# main.net
KiCad netlist of a schematic drawn in EAGLE
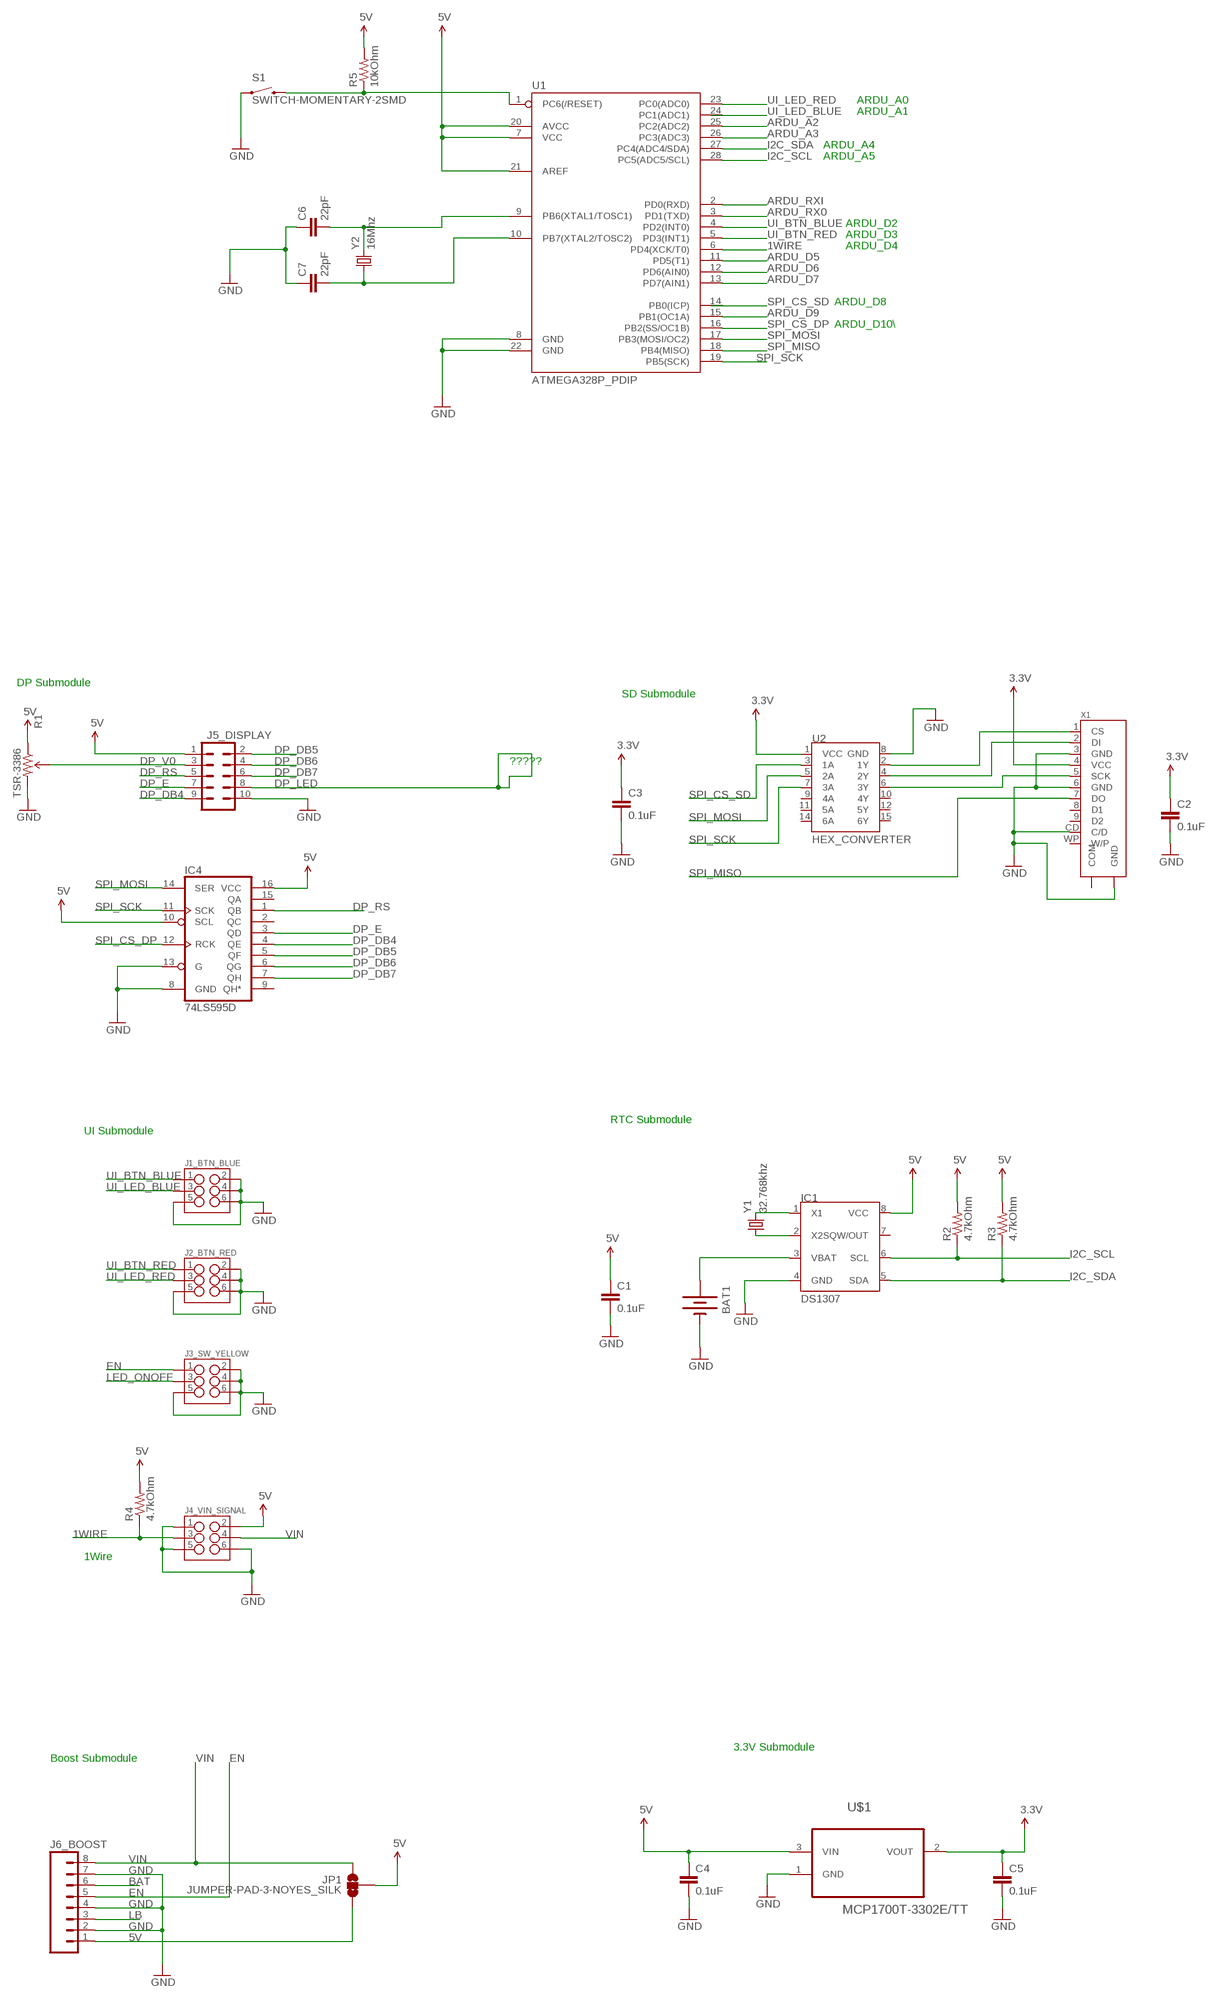
[diagram p0: schematic, sheet 1]

(export (version "E")
  (design (tool "Eeschema 10.0.6"))
  (components
    (comp (ref "BAT1")
      (value "BATTERY20PTH")
      (footprint "eagle-import:BATTCOM_20MM_PTH")
      (libsource (lib "eagle-import") (part "BATTERY20PTH"))
    )
    (comp (ref "C1")
      (value "0.1uF")
      (footprint "eagle-import:1206")
      (libsource (lib "eagle-import") (part "CAP1206"))
    )
    (comp (ref "C2")
      (value "0.1uF")
      (footprint "eagle-import:1206")
      (libsource (lib "eagle-import") (part "CAP1206"))
    )
    (comp (ref "C3")
      (value "0.1uF")
      (footprint "eagle-import:1206")
      (libsource (lib "eagle-import") (part "CAP1206"))
    )
    (comp (ref "C4")
      (value "0.1uF")
      (footprint "eagle-import:1206")
      (libsource (lib "eagle-import") (part "CAP1206"))
    )
    (comp (ref "C5")
      (value "0.1uF")
      (footprint "eagle-import:1206")
      (libsource (lib "eagle-import") (part "CAP1206"))
    )
    (comp (ref "C6")
      (value "22pF")
      (footprint "eagle-import:1206")
      (libsource (lib "eagle-import") (part "CAP1206"))
    )
    (comp (ref "C7")
      (value "22pF")
      (footprint "eagle-import:1206")
      (libsource (lib "eagle-import") (part "CAP1206"))
    )
    (comp (ref "IC1")
      (value "DS1307")
      (footprint "eagle-import:SOIC-8")
      (libsource (lib "eagle-import") (part "DS1307"))
    )
    (comp (ref "IC4")
      (value "74LS595D")
      (footprint "eagle-import:SO16")
      (libsource (lib "eagle-import") (part "74595DLS"))
    )
    (comp (ref "J1_BTN_BLUE")
      (value "M03X2SHROUD")
      (footprint "eagle-import:2X3-SHROUDED")
      (libsource (lib "eagle-import") (part "M03X2SHROUD"))
    )
    (comp (ref "J2_BTN_RED")
      (value "M03X2SHROUD")
      (footprint "eagle-import:2X3-SHROUDED")
      (libsource (lib "eagle-import") (part "M03X2SHROUD"))
    )
    (comp (ref "J3_SW_YELLOW")
      (value "M03X2SHROUD")
      (footprint "eagle-import:2X3-SHROUDED")
      (libsource (lib "eagle-import") (part "M03X2SHROUD"))
    )
    (comp (ref "J4_VIN_SIGNAL")
      (value "M03X2SHROUD")
      (footprint "eagle-import:2X3-SHROUDED")
      (libsource (lib "eagle-import") (part "M03X2SHROUD"))
    )
    (comp (ref "J5_DISPLAY")
      (value "M05X2SHD")
      (footprint "eagle-import:2X5-SHROUDED")
      (libsource (lib "eagle-import") (part "M05X2SHD"))
    )
    (comp (ref "J6_BOOST")
      (value "M08")
      (footprint "eagle-import:1X08_ROUND")
      (libsource (lib "eagle-import") (part "M08"))
    )
    (comp (ref "JP1")
      (value "JUMPER-PAD-3-NOYES_SILK")
      (footprint "eagle-import:PAD-JUMPER-3-NO_YES_SILK")
      (libsource (lib "eagle-import") (part "JUMPER-PAD-3-NOYES_SILK"))
    )
    (comp (ref "R1")
      (value "TSR-3386")
      (footprint "eagle-import:3386U")
      (libsource (lib "eagle-import") (part "TRIMPOT-PTH-KNOB"))
    )
    (comp (ref "R2")
      (value "4.7kOhm")
      (footprint "eagle-import:1206")
      (libsource (lib "eagle-import") (part "RESISTOR1206"))
    )
    (comp (ref "R3")
      (value "4.7kOhm")
      (footprint "eagle-import:1206")
      (libsource (lib "eagle-import") (part "RESISTOR1206"))
    )
    (comp (ref "R4")
      (value "4.7kOhm")
      (footprint "eagle-import:1206")
      (libsource (lib "eagle-import") (part "RESISTOR1206"))
    )
    (comp (ref "R5")
      (value "10kOhm")
      (footprint "eagle-import:1206")
      (libsource (lib "eagle-import") (part "RESISTOR1206"))
    )
    (comp (ref "S1")
      (value "SWITCH-MOMENTARY-2SMD")
      (footprint "eagle-import:TACTILE-SWITCH-SMD")
      (libsource (lib "eagle-import") (part "SWITCH-MOMENTARY-2SMD"))
    )
    (comp (ref "U$1")
      (value "MCP1700T-3302E/TT")
      (footprint "eagle-import:SOT95P237X112-3N")
      (libsource (lib "eagle-import") (part "MCP1700T-3302E/TT"))
    )
    (comp (ref "U1")
      (value "ATMEGA328P_PDIP")
      (footprint "eagle-import:DIL28-3")
      (libsource (lib "eagle-import") (part "ATMEGA328P_PDIP"))
    )
    (comp (ref "U2")
      (value "HEX_CONVERTER")
      (footprint "eagle-import:SO016")
      (libsource (lib "eagle-import") (part "HEX_CONVERTER"))
    )
    (comp (ref "X1")
      (value "SD-SOCKET-AVX")
      (footprint "eagle-import:SD-SOCKET-AVX")
      (libsource (lib "eagle-import") (part "SD-SOCKET-AVX"))
    )
    (comp (ref "Y1")
      (value "32.768khz")
      (footprint "eagle-import:CRYSTAL-32KHZ-SMD-MELF")
      (libsource (lib "eagle-import") (part "CRYSTAL32-SMD-MELF"))
    )
    (comp (ref "Y2")
      (value "16Mhz")
      (footprint "eagle-import:HC49US")
      (libsource (lib "eagle-import") (part "CRYSTALHC49US"))
    )
  )
  (nets
    (net (code "1") (name "/1WIRE") (class "Default")
      (node (ref "J4_VIN_SIGNAL") (pin "3") (pinfunction "3_3") (pintype "bidirectional"))
      (node (ref "R4") (pin "1") (pinfunction "1_1") (pintype "passive"))
      (node (ref "U1") (pin "6") (pinfunction "PD4(XCK/T0)_6") (pintype "bidirectional"))
    )
    (net (code "2") (name "/ARDU_A2") (class "Default")
      (node (ref "U1") (pin "25") (pinfunction "PC2(ADC2)_25") (pintype "bidirectional"))
    )
    (net (code "3") (name "/ARDU_A3") (class "Default")
      (node (ref "U1") (pin "26") (pinfunction "PC3(ADC3)_26") (pintype "bidirectional"))
    )
    (net (code "4") (name "/ARDU_D5") (class "Default")
      (node (ref "U1") (pin "11") (pinfunction "PD5(T1)_11") (pintype "bidirectional"))
    )
    (net (code "5") (name "/ARDU_D6") (class "Default")
      (node (ref "U1") (pin "12") (pinfunction "PD6(AIN0)_12") (pintype "bidirectional"))
    )
    (net (code "6") (name "/ARDU_D7") (class "Default")
      (node (ref "U1") (pin "13") (pinfunction "PD7(AIN1)_13") (pintype "bidirectional"))
    )
    (net (code "7") (name "/ARDU_D9") (class "Default")
      (node (ref "U1") (pin "15") (pinfunction "PB1(OC1A)_15") (pintype "bidirectional"))
    )
    (net (code "8") (name "/ARDU_RX0") (class "Default")
      (node (ref "U1") (pin "3") (pinfunction "PD1(TXD)_3") (pintype "bidirectional"))
    )
    (net (code "9") (name "/ARDU_RXI") (class "Default")
      (node (ref "U1") (pin "2") (pinfunction "PD0(RXD)_2") (pintype "bidirectional"))
    )
    (net (code "10") (name "/BAT") (class "Default")
      (node (ref "J6_BOOST") (pin "6") (pinfunction "6_6") (pintype "passive"))
    )
    (net (code "11") (name "/DP_DB4") (class "Default")
      (node (ref "IC4") (pin "4") (pinfunction "QE_4") (pintype "tri_state"))
      (node (ref "J5_DISPLAY") (pin "9") (pinfunction "9_9") (pintype "passive"))
    )
    (net (code "12") (name "/DP_DB5") (class "Default")
      (node (ref "IC4") (pin "5") (pinfunction "QF_5") (pintype "tri_state"))
      (node (ref "J5_DISPLAY") (pin "2") (pinfunction "2_2") (pintype "passive"))
    )
    (net (code "13") (name "/DP_DB6") (class "Default")
      (node (ref "IC4") (pin "6") (pinfunction "QG_6") (pintype "tri_state"))
      (node (ref "J5_DISPLAY") (pin "4") (pinfunction "4_4") (pintype "passive"))
    )
    (net (code "14") (name "/DP_DB7") (class "Default")
      (node (ref "IC4") (pin "7") (pinfunction "QH_7") (pintype "tri_state"))
      (node (ref "J5_DISPLAY") (pin "6") (pinfunction "6_6") (pintype "passive"))
    )
    (net (code "15") (name "/DP_E") (class "Default")
      (node (ref "IC4") (pin "3") (pinfunction "QD_3") (pintype "tri_state"))
      (node (ref "J5_DISPLAY") (pin "7") (pinfunction "7_7") (pintype "passive"))
    )
    (net (code "16") (name "/DP_LED") (class "Default")
      (node (ref "J5_DISPLAY") (pin "8") (pinfunction "8_8") (pintype "passive"))
    )
    (net (code "17") (name "/DP_RS") (class "Default")
      (node (ref "IC4") (pin "1") (pinfunction "QB_1") (pintype "tri_state"))
      (node (ref "J5_DISPLAY") (pin "5") (pinfunction "5_5") (pintype "passive"))
    )
    (net (code "18") (name "/DP_V0") (class "Default")
      (node (ref "J5_DISPLAY") (pin "3") (pinfunction "3_3") (pintype "passive"))
      (node (ref "R1") (pin "2") (pinfunction "WIPER_2") (pintype "passive"))
    )
    (net (code "19") (name "/EN") (class "Default")
      (node (ref "J3_SW_YELLOW") (pin "1") (pinfunction "1_1") (pintype "bidirectional"))
      (node (ref "J6_BOOST") (pin "5") (pinfunction "5_5") (pintype "passive"))
    )
    (net (code "20") (name "/I2C_SCL") (class "Default")
      (node (ref "IC1") (pin "6") (pinfunction "SCL_6") (pintype "input"))
      (node (ref "R2") (pin "1") (pinfunction "1_1") (pintype "passive"))
      (node (ref "U1") (pin "28") (pinfunction "PC5(ADC5/SCL)_28") (pintype "bidirectional"))
    )
    (net (code "21") (name "/I2C_SDA") (class "Default")
      (node (ref "IC1") (pin "5") (pinfunction "SDA_5") (pintype "bidirectional"))
      (node (ref "R3") (pin "1") (pinfunction "1_1") (pintype "passive"))
      (node (ref "U1") (pin "27") (pinfunction "PC4(ADC4/SDA)_27") (pintype "bidirectional"))
    )
    (net (code "22") (name "/LB") (class "Default")
      (node (ref "J6_BOOST") (pin "3") (pinfunction "3_3") (pintype "passive"))
    )
    (net (code "23") (name "/LED_ONOFF") (class "Default")
      (node (ref "J3_SW_YELLOW") (pin "3") (pinfunction "3_3") (pintype "bidirectional"))
    )
    (net (code "24") (name "/SPI_CS_DP") (class "Default")
      (node (ref "IC4") (pin "12") (pinfunction "RCK_12") (pintype "input"))
      (node (ref "U1") (pin "16") (pinfunction "PB2(SS/OC1B)_16") (pintype "bidirectional"))
    )
    (net (code "25") (name "/SPI_CS_SD") (class "Default")
      (node (ref "U2") (pin "3") (pinfunction "1A_3") (pintype "bidirectional"))
    )
    (net (code "26") (name "/SPI_MISO") (class "Default")
      (node (ref "U1") (pin "18") (pinfunction "PB4(MISO)_18") (pintype "bidirectional"))
      (node (ref "X1") (pin "7") (pinfunction "DO_7") (pintype "bidirectional"))
    )
    (net (code "27") (name "/SPI_MOSI") (class "Default")
      (node (ref "IC4") (pin "14") (pinfunction "SER_14") (pintype "input"))
      (node (ref "U1") (pin "17") (pinfunction "PB3(MOSI/OC2)_17") (pintype "bidirectional"))
      (node (ref "U2") (pin "5") (pinfunction "2A_5") (pintype "bidirectional"))
    )
    (net (code "28") (name "/SPI_SCK") (class "Default")
      (node (ref "IC4") (pin "11") (pinfunction "SCK_11") (pintype "input"))
      (node (ref "U1") (pin "19") (pinfunction "PB5(SCK)_19") (pintype "bidirectional"))
      (node (ref "U2") (pin "7") (pinfunction "3A_7") (pintype "bidirectional"))
    )
    (net (code "29") (name "/UI_BTN_BLUE") (class "Default")
      (node (ref "J1_BTN_BLUE") (pin "1") (pinfunction "1_1") (pintype "bidirectional"))
      (node (ref "U1") (pin "4") (pinfunction "PD2(INT0)_4") (pintype "bidirectional"))
    )
    (net (code "30") (name "/UI_BTN_RED") (class "Default")
      (node (ref "J2_BTN_RED") (pin "1") (pinfunction "1_1") (pintype "bidirectional"))
      (node (ref "U1") (pin "5") (pinfunction "PD3(INT1)_5") (pintype "bidirectional"))
    )
    (net (code "31") (name "/UI_LED_BLUE") (class "Default")
      (node (ref "J1_BTN_BLUE") (pin "3") (pinfunction "3_3") (pintype "bidirectional"))
    )
    (net (code "32") (name "/UI_LED_RED") (class "Default")
      (node (ref "J2_BTN_RED") (pin "3") (pinfunction "3_3") (pintype "bidirectional"))
      (node (ref "U1") (pin "23") (pinfunction "PC0(ADC0)_23") (pintype "bidirectional"))
    )
    (net (code "33") (name "/VIN") (class "Default")
      (node (ref "J4_VIN_SIGNAL") (pin "4") (pinfunction "4_4") (pintype "bidirectional"))
      (node (ref "J6_BOOST") (pin "8") (pinfunction "8_8") (pintype "passive"))
      (node (ref "JP1") (pin "1") (pinfunction "1_1") (pintype "passive"))
    )
    (net (code "34") (name "3.3V") (class "Default")
      (node (ref "C2") (pin "1") (pinfunction "1_1") (pintype "passive"))
      (node (ref "C3") (pin "1") (pinfunction "1_1") (pintype "passive"))
      (node (ref "C5") (pin "1") (pinfunction "1_1") (pintype "passive"))
      (node (ref "U$1") (pin "2") (pinfunction "VOUT_2") (pintype "output"))
      (node (ref "U2") (pin "1") (pinfunction "VCC_1") (pintype "bidirectional"))
      (node (ref "X1") (pin "4") (pinfunction "VCC_4") (pintype "bidirectional"))
    )
    (net (code "35") (name "5V") (class "Default")
      (node (ref "C1") (pin "1") (pinfunction "1_1") (pintype "passive"))
      (node (ref "C4") (pin "1") (pinfunction "1_1") (pintype "passive"))
      (node (ref "IC1") (pin "8") (pinfunction "VCC_8") (pintype "power_in"))
      (node (ref "IC4") (pin "10") (pinfunction "SCL_10") (pintype "input"))
      (node (ref "IC4") (pin "16") (pinfunction "VCC_16") (pintype "power_in"))
      (node (ref "J4_VIN_SIGNAL") (pin "2") (pinfunction "2_2") (pintype "bidirectional"))
      (node (ref "J5_DISPLAY") (pin "1") (pinfunction "1_1") (pintype "passive"))
      (node (ref "J6_BOOST") (pin "1") (pinfunction "1_1") (pintype "passive"))
      (node (ref "JP1") (pin "2") (pinfunction "2_2") (pintype "passive"))
      (node (ref "JP1") (pin "3") (pinfunction "3_3") (pintype "passive"))
      (node (ref "R1") (pin "1") (pinfunction "CCW_1") (pintype "passive"))
      (node (ref "R2") (pin "2") (pinfunction "2_2") (pintype "passive"))
      (node (ref "R3") (pin "2") (pinfunction "2_2") (pintype "passive"))
      (node (ref "R4") (pin "2") (pinfunction "2_2") (pintype "passive"))
      (node (ref "R5") (pin "2") (pinfunction "2_2") (pintype "passive"))
      (node (ref "U$1") (pin "3") (pinfunction "VIN_3") (pintype "input"))
      (node (ref "U1") (pin "20") (pinfunction "AVCC_20") (pintype "bidirectional"))
      (node (ref "U1") (pin "21") (pinfunction "AREF_21") (pintype "bidirectional"))
      (node (ref "U1") (pin "7") (pinfunction "VCC_7") (pintype "bidirectional"))
    )
    (net (code "36") (name "GND") (class "Default")
      (node (ref "BAT1") (pin "2") (pinfunction "-_2") (pintype "power_in"))
      (node (ref "C1") (pin "2") (pinfunction "2_2") (pintype "passive"))
      (node (ref "C2") (pin "2") (pinfunction "2_2") (pintype "passive"))
      (node (ref "C3") (pin "2") (pinfunction "2_2") (pintype "passive"))
      (node (ref "C4") (pin "2") (pinfunction "2_2") (pintype "passive"))
      (node (ref "C5") (pin "2") (pinfunction "2_2") (pintype "passive"))
      (node (ref "C6") (pin "1") (pinfunction "1_1") (pintype "passive"))
      (node (ref "C7") (pin "1") (pinfunction "1_1") (pintype "passive"))
      (node (ref "IC1") (pin "4") (pinfunction "GND_4") (pintype "power_in"))
      (node (ref "IC4") (pin "13") (pinfunction "G_13") (pintype "input"))
      (node (ref "IC4") (pin "8") (pinfunction "GND_8") (pintype "power_in"))
      (node (ref "J1_BTN_BLUE") (pin "2") (pinfunction "2_2") (pintype "bidirectional"))
      (node (ref "J1_BTN_BLUE") (pin "4") (pinfunction "4_4") (pintype "bidirectional"))
      (node (ref "J1_BTN_BLUE") (pin "5") (pinfunction "5_5") (pintype "bidirectional"))
      (node (ref "J1_BTN_BLUE") (pin "6") (pinfunction "6_6") (pintype "bidirectional"))
      (node (ref "J2_BTN_RED") (pin "2") (pinfunction "2_2") (pintype "bidirectional"))
      (node (ref "J2_BTN_RED") (pin "4") (pinfunction "4_4") (pintype "bidirectional"))
      (node (ref "J2_BTN_RED") (pin "5") (pinfunction "5_5") (pintype "bidirectional"))
      (node (ref "J2_BTN_RED") (pin "6") (pinfunction "6_6") (pintype "bidirectional"))
      (node (ref "J3_SW_YELLOW") (pin "2") (pinfunction "2_2") (pintype "bidirectional"))
      (node (ref "J3_SW_YELLOW") (pin "4") (pinfunction "4_4") (pintype "bidirectional"))
      (node (ref "J3_SW_YELLOW") (pin "5") (pinfunction "5_5") (pintype "bidirectional"))
      (node (ref "J3_SW_YELLOW") (pin "6") (pinfunction "6_6") (pintype "bidirectional"))
      (node (ref "J4_VIN_SIGNAL") (pin "1") (pinfunction "1_1") (pintype "bidirectional"))
      (node (ref "J4_VIN_SIGNAL") (pin "5") (pinfunction "5_5") (pintype "bidirectional"))
      (node (ref "J4_VIN_SIGNAL") (pin "6") (pinfunction "6_6") (pintype "bidirectional"))
      (node (ref "J5_DISPLAY") (pin "10") (pinfunction "10_10") (pintype "passive"))
      (node (ref "J6_BOOST") (pin "2") (pinfunction "2_2") (pintype "passive"))
      (node (ref "J6_BOOST") (pin "4") (pinfunction "4_4") (pintype "passive"))
      (node (ref "J6_BOOST") (pin "7") (pinfunction "7_7") (pintype "passive"))
      (node (ref "R1") (pin "3") (pinfunction "CW_3") (pintype "passive"))
      (node (ref "S1") (pin "1") (pinfunction "1_1") (pintype "passive"))
      (node (ref "U$1") (pin "1") (pinfunction "GND_1") (pintype "passive"))
      (node (ref "U1") (pin "22") (pinfunction "GND_22") (pintype "bidirectional"))
      (node (ref "U1") (pin "8") (pinfunction "GND_8") (pintype "bidirectional"))
      (node (ref "U2") (pin "8") (pinfunction "GND_8") (pintype "bidirectional"))
      (node (ref "X1") (pin "3") (pinfunction "GND_3") (pintype "bidirectional"))
      (node (ref "X1") (pin "6") (pinfunction "GND_6") (pintype "bidirectional"))
      (node (ref "X1") (pin "CD") (pinfunction "C/D_CD") (pintype "bidirectional"))
      (node (ref "X1") (pin "GND@2") (pinfunction "GND_GND@2") (pintype "bidirectional"))
    )
    (net (code "37") (name "Net-(BAT1-+)") (class "Default")
      (node (ref "BAT1") (pin "1") (pinfunction "+_1") (pintype "power_in"))
      (node (ref "IC1") (pin "3") (pinfunction "VBAT_3") (pintype "power_in"))
    )
    (net (code "38") (name "Net-(IC1-X1)") (class "Default")
      (node (ref "IC1") (pin "1") (pinfunction "X1_1") (pintype "input"))
      (node (ref "Y1") (pin "X2") (pinfunction "2_X2") (pintype "passive"))
    )
    (net (code "39") (name "Net-(IC1-X2)") (class "Default")
      (node (ref "IC1") (pin "2") (pinfunction "X2_2") (pintype "output"))
      (node (ref "Y1") (pin "X1") (pinfunction "1_X1") (pintype "passive"))
    )
    (net (code "40") (name "Net-(S1-2)") (class "Default")
      (node (ref "R5") (pin "1") (pinfunction "1_1") (pintype "passive"))
      (node (ref "S1") (pin "3") (pinfunction "2_3") (pintype "passive"))
      (node (ref "U1") (pin "1") (pinfunction "PC6(/RESET)_1") (pintype "bidirectional"))
    )
    (net (code "41") (name "Net-(U1-PB6(XTAL1{slash}TOSC1))") (class "Default")
      (node (ref "C6") (pin "2") (pinfunction "2_2") (pintype "passive"))
      (node (ref "U1") (pin "9") (pinfunction "PB6(XTAL1/TOSC1)_9") (pintype "bidirectional"))
      (node (ref "Y2") (pin "2") (pinfunction "2_2") (pintype "passive"))
    )
    (net (code "42") (name "Net-(U1-PB7(XTAL2{slash}TOSC2))") (class "Default")
      (node (ref "C7") (pin "2") (pinfunction "2_2") (pintype "passive"))
      (node (ref "U1") (pin "10") (pinfunction "PB7(XTAL2/TOSC2)_10") (pintype "bidirectional"))
      (node (ref "Y2") (pin "1") (pinfunction "1_1") (pintype "passive"))
    )
    (net (code "43") (name "Net-(U2-1Y)") (class "Default")
      (node (ref "U2") (pin "2") (pinfunction "1Y_2") (pintype "bidirectional"))
      (node (ref "X1") (pin "1") (pinfunction "CS_1") (pintype "bidirectional"))
    )
    (net (code "44") (name "Net-(U2-2Y)") (class "Default")
      (node (ref "U2") (pin "4") (pinfunction "2Y_4") (pintype "bidirectional"))
      (node (ref "X1") (pin "2") (pinfunction "DI_2") (pintype "bidirectional"))
    )
    (net (code "45") (name "Net-(U2-3Y)") (class "Default")
      (node (ref "U2") (pin "6") (pinfunction "3Y_6") (pintype "bidirectional"))
      (node (ref "X1") (pin "5") (pinfunction "SCK_5") (pintype "bidirectional"))
    )
    (net (code "46") (name "unconnected-(IC1-SQW{slash}OUT-Pad7)") (class "Default")
      (node (ref "IC1") (pin "7") (pinfunction "SQW/OUT_7") (pintype "output"))
    )
    (net (code "47") (name "unconnected-(IC4-QA-Pad15)") (class "Default")
      (node (ref "IC4") (pin "15") (pinfunction "QA_15") (pintype "tri_state"))
    )
    (net (code "48") (name "unconnected-(IC4-QC-Pad2)") (class "Default")
      (node (ref "IC4") (pin "2") (pinfunction "QC_2") (pintype "tri_state"))
    )
    (net (code "49") (name "unconnected-(IC4-QH*-Pad9)") (class "Default")
      (node (ref "IC4") (pin "9") (pinfunction "QH*_9") (pintype "tri_state"))
    )
    (net (code "50") (name "unconnected-(U1-PB0(ICP)-Pad14)") (class "Default")
      (node (ref "U1") (pin "14") (pinfunction "PB0(ICP)_14") (pintype "bidirectional"))
    )
    (net (code "51") (name "unconnected-(U1-PC1(ADC1)-Pad24)") (class "Default")
      (node (ref "U1") (pin "24") (pinfunction "PC1(ADC1)_24") (pintype "bidirectional"))
    )
    (net (code "52") (name "unconnected-(U2-4A-Pad9)") (class "Default")
      (node (ref "U2") (pin "9") (pinfunction "4A_9") (pintype "bidirectional"))
    )
    (net (code "53") (name "unconnected-(U2-4Y-Pad10)") (class "Default")
      (node (ref "U2") (pin "10") (pinfunction "4Y_10") (pintype "bidirectional"))
    )
    (net (code "54") (name "unconnected-(U2-5A-Pad11)") (class "Default")
      (node (ref "U2") (pin "11") (pinfunction "5A_11") (pintype "bidirectional"))
    )
    (net (code "55") (name "unconnected-(U2-5Y-Pad12)") (class "Default")
      (node (ref "U2") (pin "12") (pinfunction "5Y_12") (pintype "bidirectional"))
    )
    (net (code "56") (name "unconnected-(U2-6A-Pad14)") (class "Default")
      (node (ref "U2") (pin "14") (pinfunction "6A_14") (pintype "bidirectional"))
    )
    (net (code "57") (name "unconnected-(U2-6Y-Pad15)") (class "Default")
      (node (ref "U2") (pin "15") (pinfunction "6Y_15") (pintype "bidirectional"))
    )
    (net (code "58") (name "unconnected-(X1-D1-Pad8)") (class "Default")
      (node (ref "X1") (pin "8") (pinfunction "D1_8") (pintype "bidirectional"))
    )
    (net (code "59") (name "unconnected-(X1-D2-Pad9)") (class "Default")
      (node (ref "X1") (pin "9") (pinfunction "D2_9") (pintype "bidirectional"))
    )
    (net (code "60") (name "unconnected-(X1-PadCOM)") (class "Default")
      (node (ref "X1") (pin "COM") (pinfunction "COM_COM") (pintype "bidirectional"))
    )
    (net (code "61") (name "unconnected-(X1-W{slash}P-PadWP)") (class "Default")
      (node (ref "X1") (pin "WP") (pinfunction "W/P_WP") (pintype "bidirectional"))
    )
  )
)
